# Joy2PS2_rev2_3.net
KiCad netlist of a schematic drawn in EAGLE
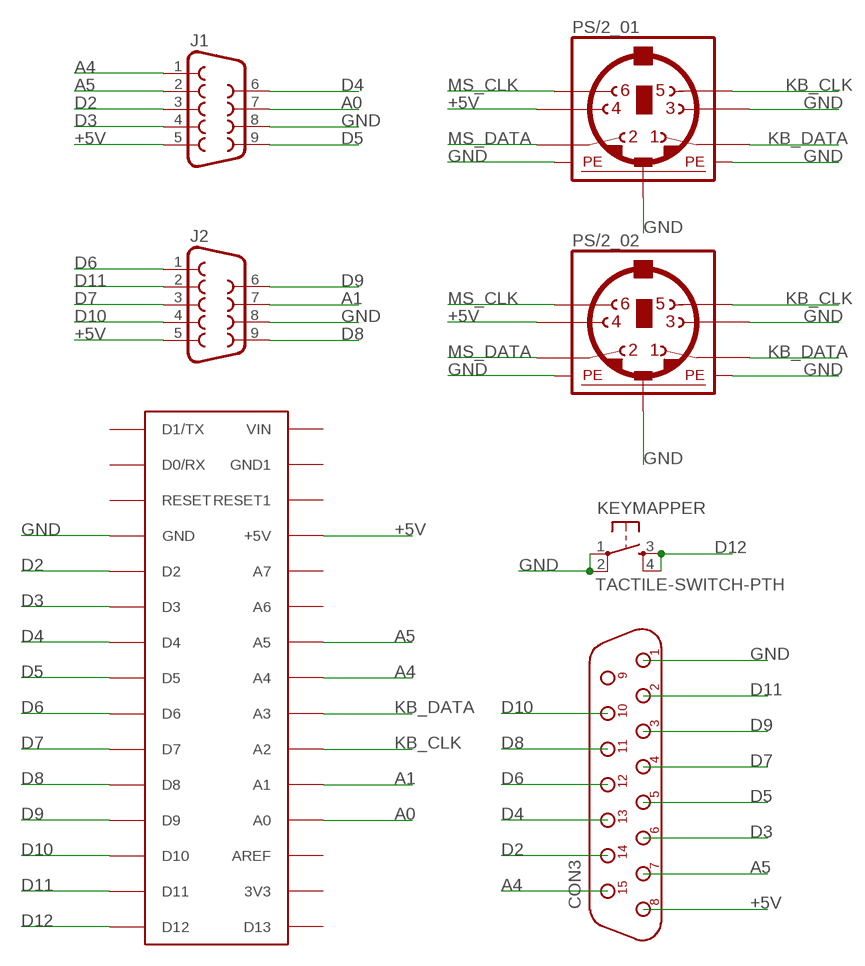
[diagram p0: schematic, sheet 1]

(export (version "E")
  (design (tool "Eeschema 10.0.6"))
  (components
    (comp (ref "ARDUINONANO")
      (value "ARDUINONANO")
      (footprint "eagle-import:PDIP-32")
      (libsource (lib "eagle-import") (part "ARDUINONANO"))
    )
    (comp (ref "CON3")
      (value "DB15M/90")
      (footprint "eagle-import:D-15M_90")
      (libsource (lib "eagle-import") (part "DB15M/90"))
    )
    (comp (ref "J1")
      (value "DB9MALE")
      (footprint "eagle-import:DB9_MALE")
      (libsource (lib "eagle-import") (part "DB9MALE"))
    )
    (comp (ref "J2")
      (value "DB9MALE")
      (footprint "eagle-import:DB9_MALE")
      (libsource (lib "eagle-import") (part "DB9MALE"))
    )
    (comp (ref "KEYMAPPER")
      (value "TACTILE-SWITCH-PTH")
      (footprint "eagle-import:TAC-SWITCH-PTH")
      (libsource (lib "eagle-import") (part "TACTILE-SWITCH-PTH"))
    )
    (comp (ref "PS/2_01")
      (value "MINI_DIN_6")
      (footprint "eagle-import:M_DIN6")
      (libsource (lib "eagle-import") (part "MINI_DIN_6"))
    )
    (comp (ref "PS/2_02")
      (value "MINI_DIN_6")
      (footprint "eagle-import:M_DIN6")
      (libsource (lib "eagle-import") (part "MINI_DIN_6"))
    )
  )
  (nets
    (net (code "1") (name "/+5V") (class "Default")
      (node (ref "ARDUINONANO") (pin "+5V") (pinfunction "+5V_+5V") (pintype "bidirectional"))
      (node (ref "CON3") (pin "8") (pinfunction "8_8") (pintype "passive"))
      (node (ref "J1") (pin "5") (pinfunction "5_5") (pintype "passive"))
      (node (ref "J2") (pin "5") (pinfunction "5_5") (pintype "passive"))
      (node (ref "PS/2_01") (pin "4") (pinfunction "4_4") (pintype "passive"))
      (node (ref "PS/2_02") (pin "4") (pinfunction "4_4") (pintype "passive"))
    )
    (net (code "2") (name "/A0") (class "Default")
      (node (ref "ARDUINONANO") (pin "A0") (pinfunction "A0_A0") (pintype "bidirectional"))
      (node (ref "J1") (pin "7") (pinfunction "7_7") (pintype "passive"))
    )
    (net (code "3") (name "/A1") (class "Default")
      (node (ref "ARDUINONANO") (pin "A1") (pinfunction "A1_A1") (pintype "bidirectional"))
      (node (ref "J2") (pin "7") (pinfunction "7_7") (pintype "passive"))
    )
    (net (code "4") (name "/A4") (class "Default")
      (node (ref "ARDUINONANO") (pin "A4") (pinfunction "A4_A4") (pintype "bidirectional"))
      (node (ref "CON3") (pin "15") (pinfunction "15_15") (pintype "passive"))
      (node (ref "J1") (pin "1") (pinfunction "1_1") (pintype "passive"))
    )
    (net (code "5") (name "/A5") (class "Default")
      (node (ref "ARDUINONANO") (pin "A5") (pinfunction "A5_A5") (pintype "bidirectional"))
      (node (ref "CON3") (pin "7") (pinfunction "7_7") (pintype "passive"))
      (node (ref "J1") (pin "2") (pinfunction "2_2") (pintype "passive"))
    )
    (net (code "6") (name "/D2") (class "Default")
      (node (ref "ARDUINONANO") (pin "D2") (pinfunction "D2_D2") (pintype "bidirectional"))
      (node (ref "CON3") (pin "14") (pinfunction "14_14") (pintype "passive"))
      (node (ref "J1") (pin "3") (pinfunction "3_3") (pintype "passive"))
    )
    (net (code "7") (name "/D3") (class "Default")
      (node (ref "ARDUINONANO") (pin "D3") (pinfunction "D3_D3") (pintype "bidirectional"))
      (node (ref "CON3") (pin "6") (pinfunction "6_6") (pintype "passive"))
      (node (ref "J1") (pin "4") (pinfunction "4_4") (pintype "passive"))
    )
    (net (code "8") (name "/D4") (class "Default")
      (node (ref "ARDUINONANO") (pin "D4") (pinfunction "D4_D4") (pintype "bidirectional"))
      (node (ref "CON3") (pin "13") (pinfunction "13_13") (pintype "passive"))
      (node (ref "J1") (pin "6") (pinfunction "6_6") (pintype "passive"))
    )
    (net (code "9") (name "/D5") (class "Default")
      (node (ref "ARDUINONANO") (pin "D5") (pinfunction "D5_D5") (pintype "bidirectional"))
      (node (ref "CON3") (pin "5") (pinfunction "5_5") (pintype "passive"))
      (node (ref "J1") (pin "9") (pinfunction "9_9") (pintype "passive"))
    )
    (net (code "10") (name "/D6") (class "Default")
      (node (ref "ARDUINONANO") (pin "D6") (pinfunction "D6_D6") (pintype "bidirectional"))
      (node (ref "CON3") (pin "12") (pinfunction "12_12") (pintype "passive"))
      (node (ref "J2") (pin "1") (pinfunction "1_1") (pintype "passive"))
    )
    (net (code "11") (name "/D7") (class "Default")
      (node (ref "ARDUINONANO") (pin "D7") (pinfunction "D7_D7") (pintype "bidirectional"))
      (node (ref "CON3") (pin "4") (pinfunction "4_4") (pintype "passive"))
      (node (ref "J2") (pin "3") (pinfunction "3_3") (pintype "passive"))
    )
    (net (code "12") (name "/D8") (class "Default")
      (node (ref "ARDUINONANO") (pin "D8") (pinfunction "D8_D8") (pintype "bidirectional"))
      (node (ref "CON3") (pin "11") (pinfunction "11_11") (pintype "passive"))
      (node (ref "J2") (pin "9") (pinfunction "9_9") (pintype "passive"))
    )
    (net (code "13") (name "/D9") (class "Default")
      (node (ref "ARDUINONANO") (pin "D9") (pinfunction "D9_D9") (pintype "bidirectional"))
      (node (ref "CON3") (pin "3") (pinfunction "3_3") (pintype "passive"))
      (node (ref "J2") (pin "6") (pinfunction "6_6") (pintype "passive"))
    )
    (net (code "14") (name "/D10") (class "Default")
      (node (ref "ARDUINONANO") (pin "D10") (pinfunction "D10_D10") (pintype "bidirectional"))
      (node (ref "CON3") (pin "10") (pinfunction "10_10") (pintype "passive"))
      (node (ref "J2") (pin "4") (pinfunction "4_4") (pintype "passive"))
    )
    (net (code "15") (name "/D11") (class "Default")
      (node (ref "ARDUINONANO") (pin "D11") (pinfunction "D11_D11") (pintype "bidirectional"))
      (node (ref "CON3") (pin "2") (pinfunction "2_2") (pintype "passive"))
      (node (ref "J2") (pin "2") (pinfunction "2_2") (pintype "passive"))
    )
    (net (code "16") (name "/D12") (class "Default")
      (node (ref "ARDUINONANO") (pin "D12") (pinfunction "D12_D12") (pintype "bidirectional"))
      (node (ref "KEYMAPPER") (pin "3") (pinfunction "3_3") (pintype "passive"))
      (node (ref "KEYMAPPER") (pin "4") (pinfunction "4_4") (pintype "passive"))
    )
    (net (code "17") (name "/GND") (class "Default")
      (node (ref "ARDUINONANO") (pin "GND") (pinfunction "GND_GND") (pintype "bidirectional"))
      (node (ref "CON3") (pin "1") (pinfunction "1_1") (pintype "passive"))
      (node (ref "J1") (pin "8") (pinfunction "8_8") (pintype "passive"))
      (node (ref "J2") (pin "8") (pinfunction "8_8") (pintype "passive"))
      (node (ref "KEYMAPPER") (pin "1") (pinfunction "1_1") (pintype "passive"))
      (node (ref "KEYMAPPER") (pin "2") (pinfunction "2_2") (pintype "passive"))
      (node (ref "PS/2_01") (pin "3") (pinfunction "3_3") (pintype "passive"))
      (node (ref "PS/2_01") (pin "SH1") (pinfunction "PE1_SH1") (pintype "power_in"))
      (node (ref "PS/2_01") (pin "SH2") (pinfunction "PE2_SH2") (pintype "power_in"))
      (node (ref "PS/2_01") (pin "SH3") (pinfunction "PE3_SH3") (pintype "power_in"))
      (node (ref "PS/2_02") (pin "3") (pinfunction "3_3") (pintype "passive"))
      (node (ref "PS/2_02") (pin "SH1") (pinfunction "PE1_SH1") (pintype "power_in"))
      (node (ref "PS/2_02") (pin "SH2") (pinfunction "PE2_SH2") (pintype "power_in"))
      (node (ref "PS/2_02") (pin "SH3") (pinfunction "PE3_SH3") (pintype "power_in"))
    )
    (net (code "18") (name "/KB_CLK") (class "Default")
      (node (ref "ARDUINONANO") (pin "A2") (pinfunction "A2_A2") (pintype "bidirectional"))
      (node (ref "PS/2_01") (pin "5") (pinfunction "5_5") (pintype "passive"))
      (node (ref "PS/2_02") (pin "5") (pinfunction "5_5") (pintype "passive"))
    )
    (net (code "19") (name "/KB_DATA") (class "Default")
      (node (ref "ARDUINONANO") (pin "A3") (pinfunction "A3_A3") (pintype "bidirectional"))
      (node (ref "PS/2_01") (pin "1") (pinfunction "1_1") (pintype "passive"))
      (node (ref "PS/2_02") (pin "1") (pinfunction "1_1") (pintype "passive"))
    )
    (net (code "20") (name "/MS_CLK") (class "Default")
      (node (ref "PS/2_01") (pin "6") (pinfunction "6_6") (pintype "passive"))
      (node (ref "PS/2_02") (pin "6") (pinfunction "6_6") (pintype "passive"))
    )
    (net (code "21") (name "/MS_DATA") (class "Default")
      (node (ref "PS/2_01") (pin "2") (pinfunction "2_2") (pintype "passive"))
      (node (ref "PS/2_02") (pin "2") (pinfunction "2_2") (pintype "passive"))
    )
    (net (code "22") (name "unconnected-(ARDUINONANO-Pad3V3)") (class "Default")
      (node (ref "ARDUINONANO") (pin "3V3") (pinfunction "3V3_3V3") (pintype "bidirectional"))
    )
    (net (code "23") (name "unconnected-(ARDUINONANO-PadA6)") (class "Default")
      (node (ref "ARDUINONANO") (pin "A6") (pinfunction "A6_A6") (pintype "bidirectional"))
    )
    (net (code "24") (name "unconnected-(ARDUINONANO-PadA7)") (class "Default")
      (node (ref "ARDUINONANO") (pin "A7") (pinfunction "A7_A7") (pintype "bidirectional"))
    )
    (net (code "25") (name "unconnected-(ARDUINONANO-PadAREF)") (class "Default")
      (node (ref "ARDUINONANO") (pin "AREF") (pinfunction "AREF_AREF") (pintype "bidirectional"))
    )
    (net (code "26") (name "unconnected-(ARDUINONANO-PadD0{slash}RX)") (class "Default")
      (node (ref "ARDUINONANO") (pin "D0/RX") (pinfunction "D0/RX_D0/RX") (pintype "bidirectional"))
    )
    (net (code "27") (name "unconnected-(ARDUINONANO-PadD1{slash}TX)") (class "Default")
      (node (ref "ARDUINONANO") (pin "D1/TX") (pinfunction "D1/TX_D1/TX") (pintype "bidirectional"))
    )
    (net (code "28") (name "unconnected-(ARDUINONANO-PadD13)") (class "Default")
      (node (ref "ARDUINONANO") (pin "D13") (pinfunction "D13_D13") (pintype "bidirectional"))
    )
    (net (code "29") (name "unconnected-(ARDUINONANO-PadGND1)") (class "Default")
      (node (ref "ARDUINONANO") (pin "GND1") (pinfunction "GND1_GND1") (pintype "bidirectional"))
    )
    (net (code "30") (name "unconnected-(ARDUINONANO-PadRESET)") (class "Default")
      (node (ref "ARDUINONANO") (pin "RESET") (pinfunction "RESET_RESET") (pintype "bidirectional"))
    )
    (net (code "31") (name "unconnected-(ARDUINONANO-PadRESET1)") (class "Default")
      (node (ref "ARDUINONANO") (pin "RESET1") (pinfunction "RESET1_RESET1") (pintype "bidirectional"))
    )
    (net (code "32") (name "unconnected-(ARDUINONANO-PadVIN)") (class "Default")
      (node (ref "ARDUINONANO") (pin "VIN") (pinfunction "VIN_VIN") (pintype "bidirectional"))
    )
    (net (code "33") (name "unconnected-(CON3-Pad9)") (class "Default")
      (node (ref "CON3") (pin "9") (pinfunction "9_9") (pintype "passive"))
    )
  )
)
